# Projeto_FonteDeTensao.net
KiCad netlist of a schematic drawn in EAGLE
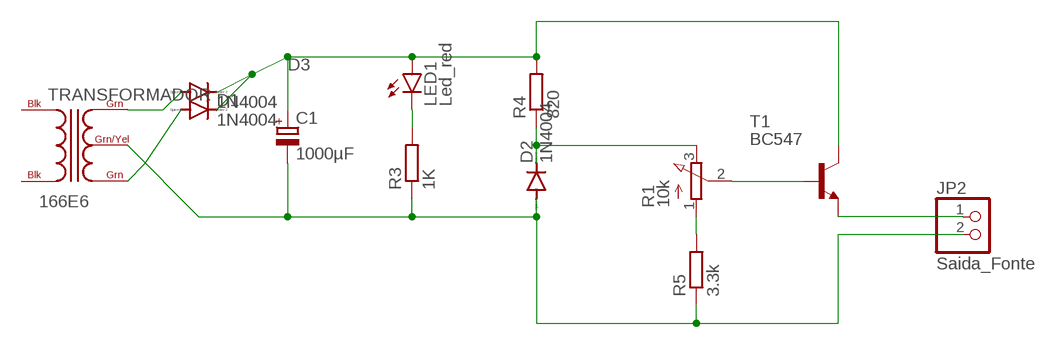
[diagram p0: schematic, sheet 1]

(export (version "E")
  (design (tool "Eeschema 10.0.6"))
  (components
    (comp (ref "C1")
      (value "1000µF")
      (footprint "eagle-import:E5-10,5")
      (libsource (lib "eagle-import") (part "CPOL-EUE5-10.5"))
    )
    (comp (ref "D1")
      (value "1N4004")
      (footprint "eagle-import:DO41-10")
      (libsource (lib "eagle-import") (part "1N4004"))
    )
    (comp (ref "D2")
      (value "1N4004")
      (footprint "eagle-import:DO41-10")
      (libsource (lib "eagle-import") (part "1N4004"))
    )
    (comp (ref "D3")
      (value "1N4004")
      (footprint "eagle-import:DO41-10")
      (libsource (lib "eagle-import") (part "1N4004"))
    )
    (comp (ref "JP2")
      (value "Saida_Fonte")
      (footprint "eagle-import:1X02")
      (libsource (lib "eagle-import") (part "PINHD-1X2"))
    )
    (comp (ref "LED1")
      (value "Led_red")
      (footprint "eagle-import:LED5MM")
      (libsource (lib "eagle-import") (part "LED5MM"))
    )
    (comp (ref "R1")
      (value "10k")
      (footprint "eagle-import:3RP_1610N")
      (libsource (lib "eagle-import") (part "3RP/1610N"))
    )
    (comp (ref "R3")
      (value "1K")
      (footprint "eagle-import:0207_10")
      (libsource (lib "eagle-import") (part "R-EU_0207/10"))
    )
    (comp (ref "R4")
      (value "820")
      (footprint "eagle-import:0207_10")
      (libsource (lib "eagle-import") (part "R-EU_0207/10"))
    )
    (comp (ref "R5")
      (value "3.3k")
      (footprint "eagle-import:0207_10")
      (libsource (lib "eagle-import") (part "R-EU_0207/10"))
    )
    (comp (ref "T1")
      (value "BC547")
      (footprint "eagle-import:TO92")
      (libsource (lib "eagle-import") (part "BC547"))
    )
    (comp (ref "TRANSFORMADOR")
      (value "166E6")
      (footprint "eagle-import:C2H")
      (libsource (lib "eagle-import") (part "166E6"))
    )
  )
  (nets
    (net (code "1") (name "Net-(C1-Pad-)") (class "Default")
      (node (ref "C1") (pin "-") (pinfunction "-_-") (pintype "passive"))
      (node (ref "D2") (pin "A") (pinfunction "A_A") (pintype "passive"))
      (node (ref "JP2") (pin "2") (pinfunction "2_2") (pintype "passive"))
      (node (ref "R3") (pin "1") (pinfunction "1_1") (pintype "passive"))
      (node (ref "R5") (pin "1") (pinfunction "1_1") (pintype "passive"))
      (node (ref "TRANSFORMADOR") (pin "GRN/YEL") (pinfunction "GRN/YEL_GRN/YEL") (pintype "passive"))
    )
    (net (code "2") (name "Net-(D1-PadA)") (class "Default")
      (node (ref "D1") (pin "A") (pinfunction "A_A") (pintype "passive"))
      (node (ref "TRANSFORMADOR") (pin "GRN@2") (pinfunction "GRN_GRN@2") (pintype "passive"))
    )
    (net (code "3") (name "Net-(D3-PadA)") (class "Default")
      (node (ref "D3") (pin "A") (pinfunction "A_A") (pintype "passive"))
      (node (ref "TRANSFORMADOR") (pin "GRN@1") (pinfunction "GRN_GRN@1") (pintype "passive"))
    )
    (net (code "4") (name "Net-(LED1-C)") (class "Default")
      (node (ref "LED1") (pin "K") (pinfunction "C_K") (pintype "passive"))
      (node (ref "R3") (pin "2") (pinfunction "2_2") (pintype "passive"))
    )
    (net (code "5") (name "Net-(R1-A)") (class "Default")
      (node (ref "R1") (pin "1") (pinfunction "A_1") (pintype "passive"))
      (node (ref "R5") (pin "2") (pinfunction "2_2") (pintype "passive"))
    )
    (net (code "6") (name "Net-(R1-E)") (class "Default")
      (node (ref "D2") (pin "C") (pinfunction "C_C") (pintype "passive"))
      (node (ref "R1") (pin "3") (pinfunction "E_3") (pintype "passive"))
      (node (ref "R4") (pin "1") (pinfunction "1_1") (pintype "passive"))
    )
    (net (code "7") (name "Net-(R1-S)") (class "Default")
      (node (ref "R1") (pin "2") (pinfunction "S_2") (pintype "passive"))
      (node (ref "T1") (pin "2") (pinfunction "B_2") (pintype "passive"))
    )
    (net (code "8") (name "Net-(T1-C)") (class "Default")
      (node (ref "C1") (pin "+") (pinfunction "+_+") (pintype "passive"))
      (node (ref "D1") (pin "C") (pinfunction "C_C") (pintype "passive"))
      (node (ref "D3") (pin "C") (pinfunction "C_C") (pintype "passive"))
      (node (ref "LED1") (pin "A") (pinfunction "A_A") (pintype "passive"))
      (node (ref "R4") (pin "2") (pinfunction "2_2") (pintype "passive"))
      (node (ref "T1") (pin "3") (pinfunction "C_3") (pintype "passive"))
    )
    (net (code "9") (name "Net-(T1-E)") (class "Default")
      (node (ref "JP2") (pin "1") (pinfunction "1_1") (pintype "passive"))
      (node (ref "T1") (pin "1") (pinfunction "E_1") (pintype "passive"))
    )
    (net (code "10") (name "unconnected-(TRANSFORMADOR-BLK-PadBLK@1)") (class "Default")
      (node (ref "TRANSFORMADOR") (pin "BLK@1") (pinfunction "BLK_BLK@1") (pintype "passive"))
    )
    (net (code "11") (name "unconnected-(TRANSFORMADOR-BLK-PadBLK@2)") (class "Default")
      (node (ref "TRANSFORMADOR") (pin "BLK@2") (pinfunction "BLK_BLK@2") (pintype "passive"))
    )
  )
)
